# powersupply.net
KiCad netlist of a schematic drawn in Altium Designer
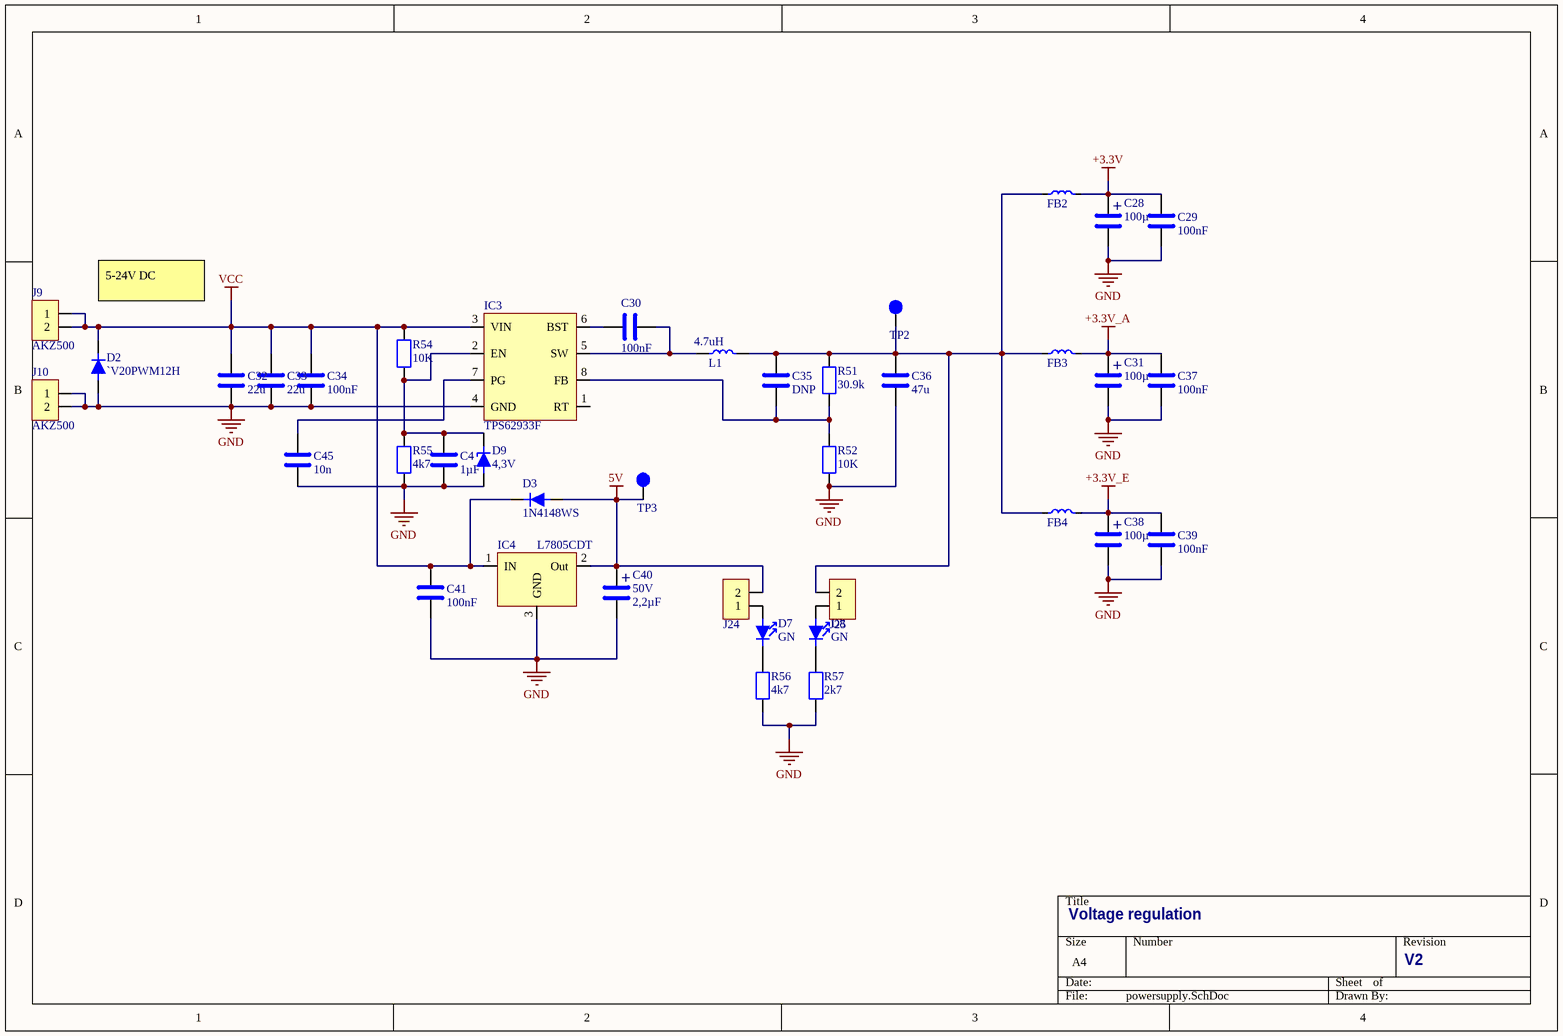
[diagram p0: powersupply.SchDoc]

(export (version "E")
  (design (tool "Eeschema 10.0.6"))
  (components
    (comp (ref "C4")
      (value "1µF")
      (footprint "0805")
      (description "1µF 25V MLCC 0805")
      (fields (field (name "VOLTAGE") "25V"))
      (libsource (lib "capacitor0805") (part "1µF 25V MLCC 0805"))
    )
    (comp (ref "C28")
      (value "100µ")
      (footprint "PANASONIC_C")
      (fields (field (name "VOLTAGE") "16V") (field (name "Comment") "Elko_100uF_16V_PanasonicC"))
      (libsource (lib "elkos") (part "Elko_100uF_16V_PanasonicC"))
    )
    (comp (ref "C29")
      (value "100nF")
      (footprint "0603")
      (description "100nF 50V MLCC 0603")
      (fields (field (name "VOLTAGE") "50V"))
      (libsource (lib "capacitors") (part "100nF 50V MLCC 0603"))
    )
    (comp (ref "C30")
      (value "100nF")
      (footprint "0603")
      (description "100nF 50V MLCC 0603")
      (fields (field (name "VOLTAGE") "50V"))
      (libsource (lib "capacitors") (part "100nF 50V MLCC 0603"))
    )
    (comp (ref "C31")
      (value "100µ")
      (footprint "PANASONIC_C")
      (fields (field (name "VOLTAGE") "16V") (field (name "Comment") "Elko_100uF_16V_PanasonicC"))
      (libsource (lib "elkos") (part "Elko_100uF_16V_PanasonicC"))
    )
    (comp (ref "C32")
      (value "22u")
      (footprint "1210")
      (description "22uF 35V X5R 1210")
      (fields (field (name "VOLTAGE") "35V"))
      (libsource (lib "capacitor1206") (part "22uF 35V X5R 1210"))
    )
    (comp (ref "C33")
      (value "22u")
      (footprint "1210")
      (description "22uF 35V X5R 1210")
      (fields (field (name "VOLTAGE") "35V"))
      (libsource (lib "capacitor1206") (part "22uF 35V X5R 1210"))
    )
    (comp (ref "C34")
      (value "100nF")
      (footprint "0603")
      (description "100nF 50V MLCC 0603")
      (fields (field (name "VOLTAGE") "50V"))
      (libsource (lib "capacitors") (part "100nF 50V MLCC 0603"))
    )
    (comp (ref "C35")
      (value "DNP")
      (footprint "0603")
      (description "680pF 50V MLCC 0603")
      (fields (field (name "Comment") "47pF MLCC 0603"))
      (libsource (lib "capacitor0603") (part "47pF MLCC 0603"))
    )
    (comp (ref "C36")
      (value "47u")
      (footprint "1210")
      (description "47uF 16V X7R 1210")
      (fields (field (name "MOUSER PART") "GRM32ER61C476KE15L") (field (name "VOLTAGE") "16V"))
      (libsource (lib "capacitor1206") (part "47uF 16V X7R 1210"))
    )
    (comp (ref "C37")
      (value "100nF")
      (footprint "0603")
      (description "100nF 50V MLCC 0603")
      (fields (field (name "VOLTAGE") "50V"))
      (libsource (lib "capacitors") (part "100nF 50V MLCC 0603"))
    )
    (comp (ref "C38")
      (value "100µ")
      (footprint "PANASONIC_C")
      (fields (field (name "VOLTAGE") "16V") (field (name "Comment") "Elko_100uF_16V_PanasonicC"))
      (libsource (lib "elkos") (part "Elko_100uF_16V_PanasonicC"))
    )
    (comp (ref "C39")
      (value "100nF")
      (footprint "0603")
      (description "100nF 50V MLCC 0603")
      (fields (field (name "VOLTAGE") "50V"))
      (libsource (lib "capacitors") (part "100nF 50V MLCC 0603"))
    )
    (comp (ref "C40")
      (value "2,2µF 50V Size B Elko")
      (footprint "SIZE_B")
      (fields (field (name "VOLTAGE") "50V") (field (name "CAPACITANCE") "2,2µF"))
      (libsource (lib "elkos") (part "2,2µF 50V Size B Elko"))
    )
    (comp (ref "C41")
      (value "100nF")
      (footprint "0603")
      (description "100nF 50V MLCC 0603")
      (fields (field (name "VOLTAGE") "50V"))
      (libsource (lib "capacitors") (part "100nF 50V MLCC 0603"))
    )
    (comp (ref "C45")
      (value "10n")
      (footprint "0603")
      (description "10nF 50V MLCC 0603")
      (fields (field (name "VOLTAGE") "50V"))
      (libsource (lib "capacitors") (part "10nF 50V MLCC 0603"))
    )
    (comp (ref "D2")
      (value "`V20PWM12H")
      (footprint "TO-252AE")
      (description "20A high power diode")
      (libsource (lib "diodes") (part "V20PWM12HM3"))
    )
    (comp (ref "D3")
      (value "1N4148WS")
      (footprint "SOD323")
      (description "Small signal diode")
      (libsource (lib "diodes") (part "1N4148WS"))
    )
    (comp (ref "D7") (value "GN") (footprint "G0805") (libsource (lib "optos") (part "G0805 LED GN")))
    (comp (ref "D8") (value "GN") (footprint "G0805") (libsource (lib "optos") (part "G0805 LED GN")))
    (comp (ref "D9")
      (value "4,3V")
      (footprint "SOD323")
      (description "4,3V Z-Diode")
      (fields (field (name "Comment") "BZT52-C4V3S_R1_00001"))
      (libsource (lib "diodes") (part "BZT52C4V3SR10000"))
    )
    (comp (ref "FB2")
      (value "HI1206N101R-10")
      (footprint "1206")
      (description "3A ferrit bead")
      (libsource (lib "inductors") (part "HI1206N101R-10"))
    )
    (comp (ref "FB3")
      (value "HI1206N101R-10")
      (footprint "1206")
      (description "3A ferrit bead")
      (libsource (lib "inductors") (part "HI1206N101R-10"))
    )
    (comp (ref "FB4")
      (value "HI1206N101R-10")
      (footprint "1206")
      (description "3A ferrit bead")
      (libsource (lib "inductors") (part "HI1206N101R-10"))
    )
    (comp (ref "IC3")
      (value "TPS62933F")
      (footprint "SOT583-8")
      (libsource (lib "regulators") (part "TPS62933F"))
    )
    (comp (ref "IC4")
      (value "L7805CDT")
      (footprint "D-PAK")
      (description "5V Spannungsregler D-PAK")
      (libsource (lib "regulators") (part "L7805CDT"))
    )
    (comp (ref "J9")
      (value "AKZ500")
      (footprint "AKZ500/2")
      (libsource (lib "connectors_screw") (part "AKZ500/2"))
    )
    (comp (ref "J10")
      (value "AKZ500")
      (footprint "AKZ500/2")
      (libsource (lib "connectors_screw") (part "AKZ500/2"))
    )
    (comp (ref "J24")
      (value "SL 1X2G 2,54")
      (footprint "SL_1x2 2.54mm")
      (description "Stiftleiste 2pol 2.54mm")
      (libsource (lib "connectors_sl") (part "SL 1X2G 2,54"))
    )
    (comp (ref "J25")
      (value "SL 1X2G 2,54")
      (footprint "SL_1x2 2.54mm")
      (description "Stiftleiste 2pol 2.54mm")
      (libsource (lib "") (part "SL 1X2G 2,54_1"))
    )
    (comp (ref "L1")
      (value "4.7uH")
      (footprint "BOURNS SRN5040")
      (fields (field (name "Comment") "SRN5040-4R7M"))
      (libsource (lib "inductors2") (part "SRN5040-4R7M"))
    )
    (comp (ref "R51")
      (value "30.9k")
      (footprint "res0603")
      (description "30k9 100mW 0603")
      (fields (field (name "TOLERANCE") "1%"))
      (libsource (lib "resistors0603") (part "30k9 100mW 0603"))
    )
    (comp (ref "R52")
      (value "10K")
      (footprint "res0603")
      (description "10K 100mW 0603")
      (fields (field (name "TOLERANCE") "1%"))
      (libsource (lib "resistors") (part "10K 100mW 0603"))
    )
    (comp (ref "R54")
      (value "10K")
      (footprint "res0603")
      (description "10K 100mW 0603")
      (fields (field (name "TOLERANCE") "1%"))
      (libsource (lib "resistors") (part "10K 100mW 0603"))
    )
    (comp (ref "R55")
      (value "4k7")
      (footprint "res0603")
      (description "4k7 100mW 0603")
      (libsource (lib "resistors") (part "4k7 100mW 0603"))
    )
    (comp (ref "R56")
      (value "4k7")
      (footprint "res0603")
      (description "4k7 100mW 0603")
      (libsource (lib "resistors") (part "4k7 100mW 0603"))
    )
    (comp (ref "R57")
      (value "2k7")
      (footprint "res0603")
      (description "2k7 100mW 0603")
      (fields (field (name "TOLERANCE") "1%"))
      (libsource (lib "resistors") (part "2k7 100mW 0603"))
    )
    (comp (ref "TP2") (value "testpoint") (footprint "testpoint") (libsource (lib "misc") (part "testpoint")))
    (comp (ref "TP3") (value "testpoint") (footprint "testpoint") (libsource (lib "misc") (part "testpoint")))
  )
  (nets
    (net (code "1") (name "+3.3V") (class "Default")
      (node (ref "C28") (pin "+") (pinfunction "+_+") (pintype "passive"))
      (node (ref "C29") (pin "1") (pinfunction "1_1") (pintype "passive"))
      (node (ref "FB2") (pin "2") (pinfunction "2_2") (pintype "passive"))
    )
    (net (code "2") (name "+3.3V_A") (class "Default")
      (node (ref "C31") (pin "+") (pinfunction "+_+") (pintype "passive"))
      (node (ref "C37") (pin "1") (pinfunction "1_1") (pintype "passive"))
      (node (ref "FB3") (pin "2") (pinfunction "2_2") (pintype "passive"))
    )
    (net (code "3") (name "+3.3V_E") (class "Default")
      (node (ref "C38") (pin "+") (pinfunction "+_+") (pintype "passive"))
      (node (ref "C39") (pin "1") (pinfunction "1_1") (pintype "passive"))
      (node (ref "FB4") (pin "2") (pinfunction "2_2") (pintype "passive"))
    )
    (net (code "4") (name "5V") (class "Default")
      (node (ref "C40") (pin "1") (pinfunction "1_1") (pintype "passive"))
      (node (ref "D3") (pin "2") (pinfunction "2_2") (pintype "passive"))
      (node (ref "IC4") (pin "2") (pinfunction "Out_2") (pintype "passive"))
      (node (ref "J24") (pin "2") (pinfunction "2_2") (pintype "passive"))
      (node (ref "TP3") (pin "1") (pinfunction "1_1") (pintype "passive"))
    )
    (net (code "5") (name "GND") (class "Default")
      (node (ref "C28") (pin "-") (pinfunction "-_-") (pintype "passive"))
      (node (ref "C29") (pin "2") (pinfunction "2_2") (pintype "passive"))
      (node (ref "C31") (pin "-") (pinfunction "-_-") (pintype "passive"))
      (node (ref "C32") (pin "2") (pinfunction "2_2") (pintype "passive"))
      (node (ref "C33") (pin "2") (pinfunction "2_2") (pintype "passive"))
      (node (ref "C34") (pin "2") (pinfunction "2_2") (pintype "passive"))
      (node (ref "C36") (pin "2") (pinfunction "2_2") (pintype "passive"))
      (node (ref "C37") (pin "2") (pinfunction "2_2") (pintype "passive"))
      (node (ref "C38") (pin "-") (pinfunction "-_-") (pintype "passive"))
      (node (ref "C39") (pin "2") (pinfunction "2_2") (pintype "passive"))
      (node (ref "C4") (pin "2") (pinfunction "2_2") (pintype "passive"))
      (node (ref "C40") (pin "2") (pinfunction "2_2") (pintype "passive"))
      (node (ref "C41") (pin "1") (pinfunction "1_1") (pintype "passive"))
      (node (ref "C45") (pin "2") (pinfunction "2_2") (pintype "passive"))
      (node (ref "D2") (pin "2") (pinfunction "2_2") (pintype "passive"))
      (node (ref "D9") (pin "2") (pinfunction "2_2") (pintype "passive"))
      (node (ref "IC3") (pin "4") (pinfunction "GND_4") (pintype "passive"))
      (node (ref "IC4") (pin "3") (pinfunction "GND_3") (pintype "passive"))
      (node (ref "J10") (pin "1") (pinfunction "1_1") (pintype "passive"))
      (node (ref "J10") (pin "2") (pinfunction "2_2") (pintype "passive"))
      (node (ref "R52") (pin "1") (pinfunction "1_1") (pintype "passive"))
      (node (ref "R55") (pin "1") (pinfunction "1_1") (pintype "passive"))
      (node (ref "R56") (pin "1") (pinfunction "1_1") (pintype "passive"))
      (node (ref "R57") (pin "1") (pinfunction "1_1") (pintype "passive"))
    )
    (net (code "6") (name "Net-(C35-Pad1)") (class "Default")
      (node (ref "C35") (pin "1") (pinfunction "1_1") (pintype "passive"))
      (node (ref "C36") (pin "1") (pinfunction "1_1") (pintype "passive"))
      (node (ref "FB2") (pin "1") (pinfunction "1_1") (pintype "passive"))
      (node (ref "FB3") (pin "1") (pinfunction "1_1") (pintype "passive"))
      (node (ref "FB4") (pin "1") (pinfunction "1_1") (pintype "passive"))
      (node (ref "J25") (pin "2") (pinfunction "2_2") (pintype "passive"))
      (node (ref "L1") (pin "2") (pinfunction "2_2") (pintype "passive"))
      (node (ref "R51") (pin "2") (pinfunction "2_2") (pintype "passive"))
      (node (ref "TP2") (pin "1") (pinfunction "1_1") (pintype "passive"))
    )
    (net (code "7") (name "Net-(D7-Pad1)") (class "Default")
      (node (ref "D7") (pin "1") (pinfunction "1_1") (pintype "passive"))
      (node (ref "R56") (pin "2") (pinfunction "2_2") (pintype "passive"))
    )
    (net (code "8") (name "Net-(D7-Pad2)") (class "Default")
      (node (ref "D7") (pin "2") (pinfunction "2_2") (pintype "passive"))
      (node (ref "J24") (pin "1") (pinfunction "1_1") (pintype "passive"))
    )
    (net (code "9") (name "Net-(D8-Pad1)") (class "Default")
      (node (ref "D8") (pin "1") (pinfunction "1_1") (pintype "passive"))
      (node (ref "R57") (pin "2") (pinfunction "2_2") (pintype "passive"))
    )
    (net (code "10") (name "Net-(D8-Pad2)") (class "Default")
      (node (ref "D8") (pin "2") (pinfunction "2_2") (pintype "passive"))
      (node (ref "J25") (pin "1") (pinfunction "1_1") (pintype "passive"))
    )
    (net (code "11") (name "Net-(IC3-BST)") (class "Default")
      (node (ref "C30") (pin "1") (pinfunction "1_1") (pintype "passive"))
      (node (ref "IC3") (pin "6") (pinfunction "BST_6") (pintype "passive"))
    )
    (net (code "12") (name "Net-(IC3-EN)") (class "Default")
      (node (ref "C4") (pin "1") (pinfunction "1_1") (pintype "passive"))
      (node (ref "D9") (pin "1") (pinfunction "1_1") (pintype "passive"))
      (node (ref "IC3") (pin "2") (pinfunction "EN_2") (pintype "passive"))
      (node (ref "R54") (pin "1") (pinfunction "1_1") (pintype "passive"))
      (node (ref "R55") (pin "2") (pinfunction "2_2") (pintype "passive"))
    )
    (net (code "13") (name "Net-(IC3-FB)") (class "Default")
      (node (ref "C35") (pin "2") (pinfunction "2_2") (pintype "passive"))
      (node (ref "IC3") (pin "8") (pinfunction "FB_8") (pintype "passive"))
      (node (ref "R51") (pin "1") (pinfunction "1_1") (pintype "passive"))
      (node (ref "R52") (pin "2") (pinfunction "2_2") (pintype "passive"))
    )
    (net (code "14") (name "Net-(IC3-PG)") (class "Default")
      (node (ref "C45") (pin "1") (pinfunction "1_1") (pintype "passive"))
      (node (ref "IC3") (pin "7") (pinfunction "PG_7") (pintype "passive"))
    )
    (net (code "15") (name "Net-(IC3-SW)") (class "Default")
      (node (ref "C30") (pin "2") (pinfunction "2_2") (pintype "passive"))
      (node (ref "IC3") (pin "5") (pinfunction "SW_5") (pintype "passive"))
      (node (ref "L1") (pin "1") (pinfunction "1_1") (pintype "passive"))
    )
    (net (code "16") (name "VCC") (class "Default")
      (node (ref "C32") (pin "1") (pinfunction "1_1") (pintype "passive"))
      (node (ref "C33") (pin "1") (pinfunction "1_1") (pintype "passive"))
      (node (ref "C34") (pin "1") (pinfunction "1_1") (pintype "passive"))
      (node (ref "C41") (pin "2") (pinfunction "2_2") (pintype "passive"))
      (node (ref "D2") (pin "1") (pinfunction "1_1") (pintype "passive"))
      (node (ref "D3") (pin "1") (pinfunction "1_1") (pintype "passive"))
      (node (ref "IC3") (pin "3") (pinfunction "VIN_3") (pintype "passive"))
      (node (ref "IC4") (pin "1") (pinfunction "IN_1") (pintype "passive"))
      (node (ref "J9") (pin "1") (pinfunction "1_1") (pintype "passive"))
      (node (ref "J9") (pin "2") (pinfunction "2_2") (pintype "passive"))
      (node (ref "R54") (pin "2") (pinfunction "2_2") (pintype "passive"))
    )
    (net (code "17") (name "unconnected-(IC3-RT-Pad1)") (class "Default")
      (node (ref "IC3") (pin "1") (pinfunction "RT_1") (pintype "passive"))
    )
  )
)
